# Output_Register.net
KiCad netlist of a schematic drawn in EasyEDA Pro
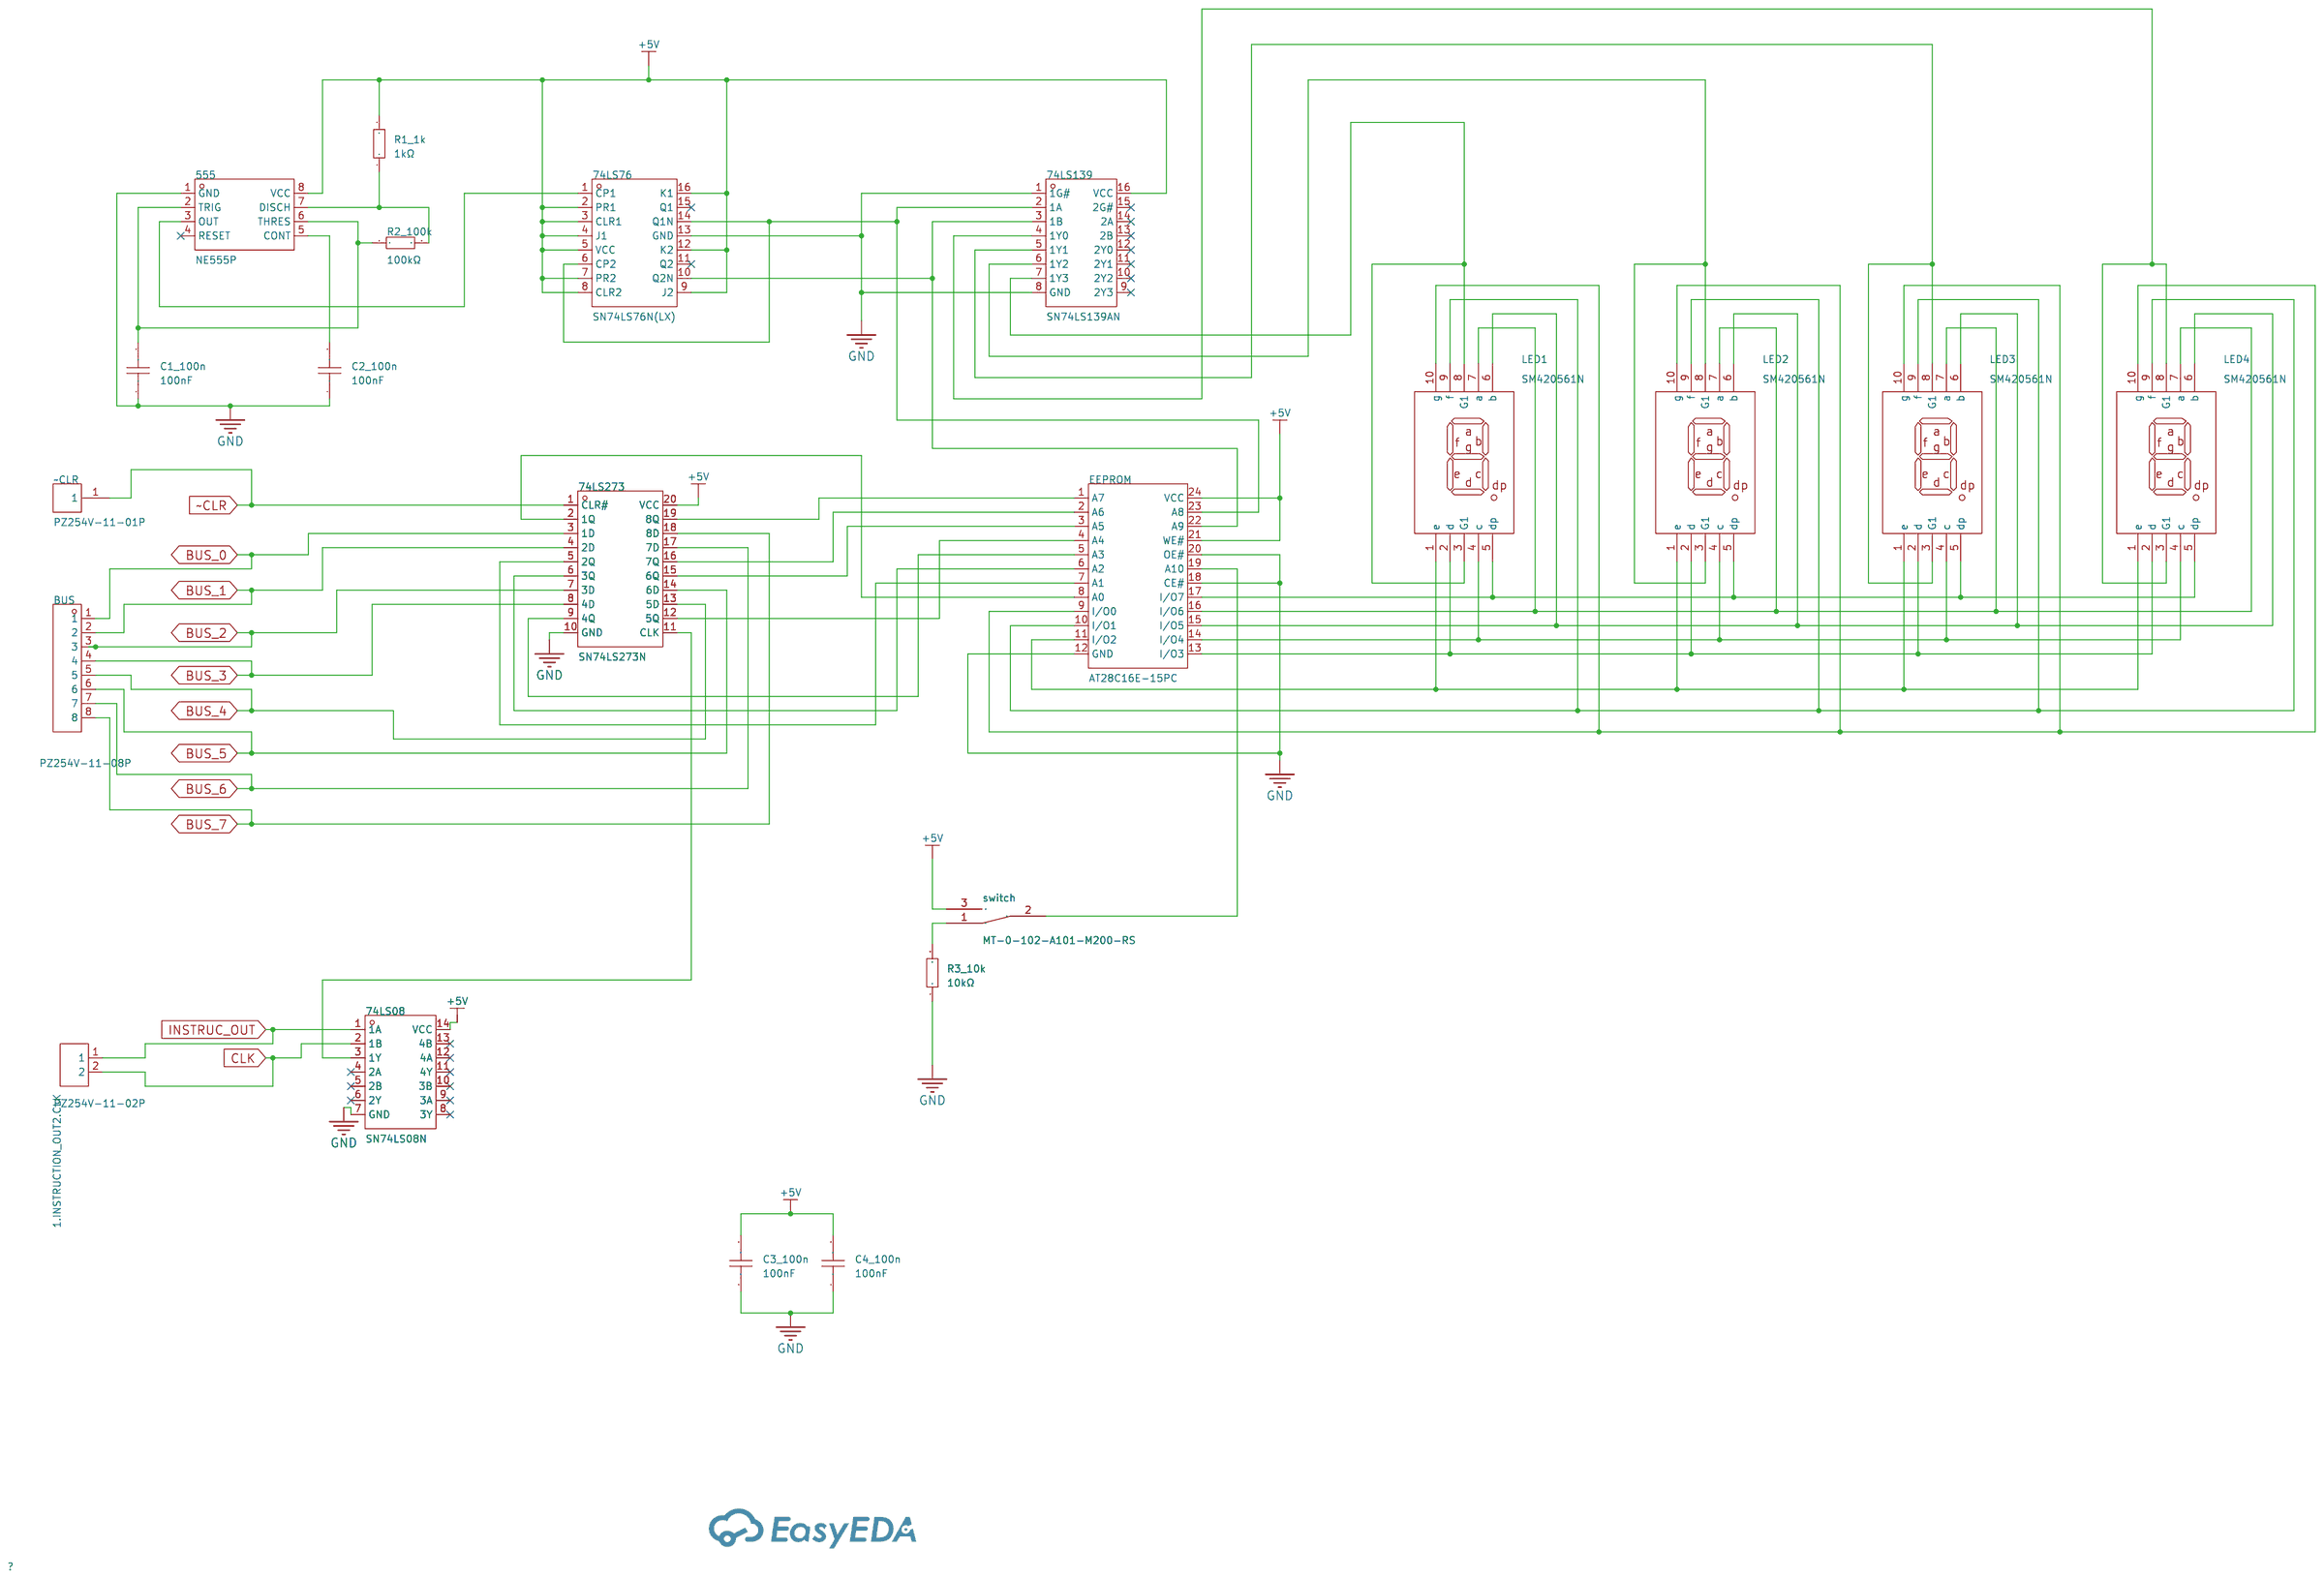
[diagram p0: schematic sheet]

(export (version "E")
  (design (tool "Eeschema 10.0.6"))
  (components
    (comp (ref "1.INSTRUCTION_OUT2.CLK")
      (value "PZ254V-11-02P")
      (footprint "easyedapro:HDR-TH_2P-P2.54-V-M")
      (fields (field (name "Manufacturer") "XFCN(兴飞)"))
      (libsource (lib "easyedapro") (part "PZ254V-11-02P"))
    )
    (comp (ref "74LS08")
      (value "SN74LS08N")
      (footprint "easyedapro:PDIP-14_L19.3-W6.4-P2.54-LS7.9-BL-1")
      (fields (field (name "Manufacturer") "TI(德州仪器)"))
      (libsource (lib "easyedapro") (part "SN74LS08N"))
    )
    (comp (ref "74LS76")
      (value "SN74LS76N(LX)")
      (footprint "easyedapro:PDIP-16_L19.3-W6.4-P2.54-LS7.94-BL")
      (fields (field (name "Manufacturer") "LX(灵星芯微)"))
      (libsource (lib "easyedapro") (part "SN74LS76N(LX)"))
    )
    (comp (ref "74LS139")
      (value "SN74LS139AN")
      (footprint "easyedapro:PDIP-16_L19.3-W6.4-P2.54-LS7.9-BL")
      (fields (field (name "Manufacturer") "TI(德州仪器)"))
      (libsource (lib "easyedapro") (part "SN74LS139AN"))
    )
    (comp (ref "74LS273")
      (value "SN74LS273N")
      (footprint "easyedapro:PDIP-20_L25.4-W6.4-P2.54-LS7.6-BL")
      (fields (field (name "Manufacturer") "TI(德州仪器)"))
      (libsource (lib "easyedapro") (part "SN74LS273N"))
    )
    (comp (ref "555")
      (value "NE555P")
      (footprint "easyedapro:DIP-8_L9.8-W6.6-P2.54-LS7.6-BL")
      (fields (field (name "Manufacturer") "TI(德州仪器)"))
      (libsource (lib "easyedapro") (part "NE555P"))
    )
    (comp (ref "BUS")
      (value "PZ254V-11-08P")
      (footprint "easyedapro:HDR-TH_8P-P2.54-V-M")
      (fields (field (name "Manufacturer") "XFCN(兴飞)"))
      (libsource (lib "easyedapro") (part "PZ254V-11-08P"))
    )
    (comp (ref "C1_100n")
      (value "100nF")
      (footprint "easyedapro:CAP-TH_L8.5-W5.0-P5.00-D1.2")
      (fields (field (name "Manufacturer Part") "CT4-0805B104K500F3") (field (name "Manufacturer") "FH(风华)"))
      (libsource (lib "easyedapro") (part "CT4-0805B104K500F3"))
    )
    (comp (ref "C2_100n")
      (value "100nF")
      (footprint "easyedapro:CAP-TH_L8.5-W5.0-P5.00-D1.2")
      (fields (field (name "Manufacturer Part") "CT4-0805B104K500F3") (field (name "Manufacturer") "FH(风华)"))
      (libsource (lib "easyedapro") (part "CT4-0805B104K500F3"))
    )
    (comp (ref "C3_100n")
      (value "100nF")
      (footprint "easyedapro:CAP-TH_L8.5-W5.0-P5.00-D1.2")
      (fields (field (name "Manufacturer Part") "CT4-0805B104K500F3") (field (name "Manufacturer") "FH(风华)"))
      (libsource (lib "easyedapro") (part "CT4-0805B104K500F3"))
    )
    (comp (ref "C4_100n")
      (value "100nF")
      (footprint "easyedapro:CAP-TH_L8.5-W5.0-P5.00-D1.2")
      (fields (field (name "Manufacturer Part") "CT4-0805B104K500F3") (field (name "Manufacturer") "FH(风华)"))
      (libsource (lib "easyedapro") (part "CT4-0805B104K500F3"))
    )
    (comp (ref "EEPROM")
      (value "AT28C16E-15PC")
      (footprint "easyedapro:PDIP-24_L31.0-W13.5-P2.54-LS15.2-BL")
      (fields (field (name "Manufacturer") "MICROCHIP(美国微芯)"))
      (libsource (lib "easyedapro") (part "AT28C16E-15PC"))
    )
    (comp (ref "LED1")
      (value "SM420561N")
      (footprint "easyedapro:LED-SEG-TH_10P-L12.7-W19.0-P2.54-S15.24-BL")
      (fields (field (name "Manufacturer") "ARKLED(方舟)"))
      (libsource (lib "easyedapro") (part "SM420561N"))
    )
    (comp (ref "LED2")
      (value "SM420561N")
      (footprint "easyedapro:LED-SEG-TH_10P-L12.7-W19.0-P2.54-S15.24-BL")
      (fields (field (name "Manufacturer") "ARKLED(方舟)"))
      (libsource (lib "easyedapro") (part "SM420561N"))
    )
    (comp (ref "LED3")
      (value "SM420561N")
      (footprint "easyedapro:LED-SEG-TH_10P-L12.7-W19.0-P2.54-S15.24-BL")
      (fields (field (name "Manufacturer") "ARKLED(方舟)"))
      (libsource (lib "easyedapro") (part "SM420561N"))
    )
    (comp (ref "LED4")
      (value "SM420561N")
      (footprint "easyedapro:LED-SEG-TH_10P-L12.7-W19.0-P2.54-S15.24-BL")
      (fields (field (name "Manufacturer") "ARKLED(方舟)"))
      (libsource (lib "easyedapro") (part "SM420561N"))
    )
    (comp (ref "R1_1k")
      (value "1kΩ")
      (footprint "easyedapro:R_AXIAL-0.4")
      (libsource (lib "easyedapro") (part "Res"))
    )
    (comp (ref "R2_100k")
      (value "100kΩ")
      (footprint "easyedapro:R_AXIAL-0.4")
      (libsource (lib "easyedapro") (part "Res"))
    )
    (comp (ref "R3_10k")
      (value "10kΩ")
      (footprint "easyedapro:R_AXIAL-0.4")
      (libsource (lib "easyedapro") (part "Res"))
    )
    (comp (ref "switch")
      (value "MT-0-102-A101-M200-RS")
      (footprint "easyedapro:SW-TH_MT-0-103-A101-M200-RS")
      (fields (field (name "Manufacturer") "YUEN FUNG(源丰)"))
      (libsource (lib "easyedapro") (part "MT-0-102-A101-M200-RS+PJ"))
    )
    (comp (ref "~CLR")
      (value "PZ254V-11-01P")
      (footprint "easyedapro:HDR-TH_1P-P2.54-V-M")
      (fields (field (name "Manufacturer") "XFCN(兴飞)"))
      (libsource (lib "easyedapro") (part "PZ254V-11-01P"))
    )
  )
  (nets
    (net (code "1") (name "+5V") (class "Default")
      (node (ref "555") (pin "8") (pinfunction "VCC_8") (pintype "input"))
      (node (ref "74LS08") (pin "14") (pinfunction "VCC_14") (pintype "unspecified"))
      (node (ref "74LS139") (pin "16") (pinfunction "VCC_16") (pintype "input"))
      (node (ref "74LS273") (pin "20") (pinfunction "VCC_20") (pintype "unspecified"))
      (node (ref "74LS76") (pin "12") (pinfunction "K2_12") (pintype "unspecified"))
      (node (ref "74LS76") (pin "16") (pinfunction "K1_16") (pintype "unspecified"))
      (node (ref "74LS76") (pin "2") (pinfunction "PR1_2") (pintype "unspecified"))
      (node (ref "74LS76") (pin "3") (pinfunction "CLR1_3") (pintype "unspecified"))
      (node (ref "74LS76") (pin "4") (pinfunction "J1_4") (pintype "unspecified"))
      (node (ref "74LS76") (pin "5") (pinfunction "VCC_5") (pintype "unspecified"))
      (node (ref "74LS76") (pin "7") (pinfunction "PR2_7") (pintype "unspecified"))
      (node (ref "74LS76") (pin "8") (pinfunction "CLR2_8") (pintype "unspecified"))
      (node (ref "74LS76") (pin "9") (pinfunction "J2_9") (pintype "unspecified"))
      (node (ref "C3_100n") (pin "2") (pinfunction "2_2") (pintype "unspecified"))
      (node (ref "C4_100n") (pin "2") (pinfunction "2_2") (pintype "unspecified"))
      (node (ref "EEPROM") (pin "21") (pinfunction "WE#_21") (pintype "unspecified"))
      (node (ref "EEPROM") (pin "24") (pinfunction "VCC_24") (pintype "unspecified"))
      (node (ref "R1_1k") (pin "2") (pinfunction "2_2") (pintype "input"))
      (node (ref "switch") (pin "3") (pinfunction "3_3") (pintype "unspecified"))
    )
    (net (code "2") (name "BUS_0") (class "Default")
      (node (ref "74LS273") (pin "3") (pinfunction "1D_3") (pintype "unspecified"))
      (node (ref "BUS") (pin "1") (pinfunction "1_1") (pintype "unspecified"))
    )
    (net (code "3") (name "BUS_1") (class "Default")
      (node (ref "74LS273") (pin "4") (pinfunction "2D_4") (pintype "unspecified"))
      (node (ref "BUS") (pin "2") (pinfunction "2_2") (pintype "unspecified"))
    )
    (net (code "4") (name "BUS_2") (class "Default")
      (node (ref "74LS273") (pin "7") (pinfunction "3D_7") (pintype "unspecified"))
      (node (ref "BUS") (pin "3") (pinfunction "3_3") (pintype "unspecified"))
    )
    (net (code "5") (name "BUS_3") (class "Default")
      (node (ref "74LS273") (pin "8") (pinfunction "4D_8") (pintype "unspecified"))
      (node (ref "BUS") (pin "4") (pinfunction "4_4") (pintype "unspecified"))
    )
    (net (code "6") (name "BUS_4") (class "Default")
      (node (ref "74LS273") (pin "13") (pinfunction "5D_13") (pintype "unspecified"))
      (node (ref "BUS") (pin "5") (pinfunction "5_5") (pintype "unspecified"))
    )
    (net (code "7") (name "BUS_5") (class "Default")
      (node (ref "74LS273") (pin "14") (pinfunction "6D_14") (pintype "unspecified"))
      (node (ref "BUS") (pin "6") (pinfunction "6_6") (pintype "unspecified"))
    )
    (net (code "8") (name "BUS_6") (class "Default")
      (node (ref "74LS273") (pin "17") (pinfunction "7D_17") (pintype "unspecified"))
      (node (ref "BUS") (pin "7") (pinfunction "7_7") (pintype "unspecified"))
    )
    (net (code "9") (name "BUS_7") (class "Default")
      (node (ref "74LS273") (pin "18") (pinfunction "8D_18") (pintype "unspecified"))
      (node (ref "BUS") (pin "8") (pinfunction "8_8") (pintype "unspecified"))
    )
    (net (code "10") (name "CLK") (class "Default")
      (node (ref "1.INSTRUCTION_OUT2.CLK") (pin "2") (pinfunction "2_2") (pintype "unspecified"))
      (node (ref "74LS08") (pin "2") (pinfunction "1B_2") (pintype "unspecified"))
    )
    (net (code "11") (name "GND") (class "Default")
      (node (ref "555") (pin "1") (pinfunction "GND_1") (pintype "input"))
      (node (ref "74LS08") (pin "7") (pinfunction "GND_7") (pintype "unspecified"))
      (node (ref "74LS139") (pin "1") (pinfunction "1G#_1") (pintype "input"))
      (node (ref "74LS139") (pin "8") (pinfunction "GND_8") (pintype "input"))
      (node (ref "74LS273") (pin "10") (pinfunction "GND_10") (pintype "unspecified"))
      (node (ref "74LS76") (pin "13") (pinfunction "GND_13") (pintype "unspecified"))
      (node (ref "C1_100n") (pin "1") (pinfunction "1_1") (pintype "unspecified"))
      (node (ref "C2_100n") (pin "1") (pinfunction "1_1") (pintype "unspecified"))
      (node (ref "C3_100n") (pin "1") (pinfunction "1_1") (pintype "unspecified"))
      (node (ref "C4_100n") (pin "1") (pinfunction "1_1") (pintype "unspecified"))
      (node (ref "EEPROM") (pin "12") (pinfunction "GND_12") (pintype "unspecified"))
      (node (ref "EEPROM") (pin "18") (pinfunction "CE#_18") (pintype "unspecified"))
      (node (ref "EEPROM") (pin "20") (pinfunction "OE#_20") (pintype "unspecified"))
      (node (ref "R3_10k") (pin "1") (pinfunction "1_1") (pintype "input"))
    )
    (net (code "12") (name "INSTRUC_OUT") (class "Default")
      (node (ref "1.INSTRUCTION_OUT2.CLK") (pin "1") (pinfunction "1_1") (pintype "unspecified"))
      (node (ref "74LS08") (pin "1") (pinfunction "1A_1") (pintype "unspecified"))
    )
    (net (code "13") (name "Net-(74LS08-1Y)") (class "Default")
      (node (ref "74LS08") (pin "3") (pinfunction "1Y_3") (pintype "unspecified"))
      (node (ref "74LS273") (pin "11") (pinfunction "CLK_11") (pintype "unspecified"))
    )
    (net (code "14") (name "Net-(74LS139-1A)") (class "Default")
      (node (ref "74LS139") (pin "2") (pinfunction "1A_2") (pintype "input"))
      (node (ref "74LS76") (pin "14") (pinfunction "Q1N_14") (pintype "unspecified"))
      (node (ref "74LS76") (pin "6") (pinfunction "CP2_6") (pintype "unspecified"))
      (node (ref "EEPROM") (pin "23") (pinfunction "A8_23") (pintype "unspecified"))
    )
    (net (code "15") (name "Net-(74LS139-1B)") (class "Default")
      (node (ref "74LS139") (pin "3") (pinfunction "1B_3") (pintype "input"))
      (node (ref "74LS76") (pin "10") (pinfunction "Q2N_10") (pintype "unspecified"))
      (node (ref "EEPROM") (pin "22") (pinfunction "A9_22") (pintype "unspecified"))
    )
    (net (code "16") (name "Net-(74LS139-1Y0)") (class "Default")
      (node (ref "74LS139") (pin "4") (pinfunction "1Y0_4") (pintype "input"))
      (node (ref "LED4") (pin "3") (pinfunction "G1_3") (pintype "input"))
      (node (ref "LED4") (pin "8") (pinfunction "G1_8") (pintype "input"))
    )
    (net (code "17") (name "Net-(74LS139-1Y1)") (class "Default")
      (node (ref "74LS139") (pin "5") (pinfunction "1Y1_5") (pintype "input"))
      (node (ref "LED3") (pin "3") (pinfunction "G1_3") (pintype "input"))
      (node (ref "LED3") (pin "8") (pinfunction "G1_8") (pintype "input"))
    )
    (net (code "18") (name "Net-(74LS139-1Y2)") (class "Default")
      (node (ref "74LS139") (pin "6") (pinfunction "1Y2_6") (pintype "input"))
      (node (ref "LED2") (pin "3") (pinfunction "G1_3") (pintype "input"))
      (node (ref "LED2") (pin "8") (pinfunction "G1_8") (pintype "input"))
    )
    (net (code "19") (name "Net-(74LS139-1Y3)") (class "Default")
      (node (ref "74LS139") (pin "7") (pinfunction "1Y3_7") (pintype "input"))
      (node (ref "LED1") (pin "3") (pinfunction "G1_3") (pintype "input"))
      (node (ref "LED1") (pin "8") (pinfunction "G1_8") (pintype "input"))
    )
    (net (code "20") (name "Net-(74LS273-1Q)") (class "Default")
      (node (ref "74LS273") (pin "2") (pinfunction "1Q_2") (pintype "unspecified"))
      (node (ref "EEPROM") (pin "8") (pinfunction "A0_8") (pintype "unspecified"))
    )
    (net (code "21") (name "Net-(74LS273-2Q)") (class "Default")
      (node (ref "74LS273") (pin "5") (pinfunction "2Q_5") (pintype "unspecified"))
      (node (ref "EEPROM") (pin "7") (pinfunction "A1_7") (pintype "unspecified"))
    )
    (net (code "22") (name "Net-(74LS273-3Q)") (class "Default")
      (node (ref "74LS273") (pin "6") (pinfunction "3Q_6") (pintype "unspecified"))
      (node (ref "EEPROM") (pin "6") (pinfunction "A2_6") (pintype "unspecified"))
    )
    (net (code "23") (name "Net-(74LS273-4Q)") (class "Default")
      (node (ref "74LS273") (pin "9") (pinfunction "4Q_9") (pintype "unspecified"))
      (node (ref "EEPROM") (pin "5") (pinfunction "A3_5") (pintype "unspecified"))
    )
    (net (code "24") (name "Net-(74LS273-5Q)") (class "Default")
      (node (ref "74LS273") (pin "12") (pinfunction "5Q_12") (pintype "unspecified"))
      (node (ref "EEPROM") (pin "4") (pinfunction "A4_4") (pintype "unspecified"))
    )
    (net (code "25") (name "Net-(74LS273-6Q)") (class "Default")
      (node (ref "74LS273") (pin "15") (pinfunction "6Q_15") (pintype "unspecified"))
      (node (ref "EEPROM") (pin "3") (pinfunction "A5_3") (pintype "unspecified"))
    )
    (net (code "26") (name "Net-(74LS273-7Q)") (class "Default")
      (node (ref "74LS273") (pin "16") (pinfunction "7Q_16") (pintype "unspecified"))
      (node (ref "EEPROM") (pin "2") (pinfunction "A6_2") (pintype "unspecified"))
    )
    (net (code "27") (name "Net-(74LS273-8Q)") (class "Default")
      (node (ref "74LS273") (pin "19") (pinfunction "8Q_19") (pintype "unspecified"))
      (node (ref "EEPROM") (pin "1") (pinfunction "A7_1") (pintype "unspecified"))
    )
    (net (code "28") (name "Net-(555-CONT)") (class "Default")
      (node (ref "555") (pin "5") (pinfunction "CONT_5") (pintype "input"))
      (node (ref "C2_100n") (pin "2") (pinfunction "2_2") (pintype "unspecified"))
    )
    (net (code "29") (name "Net-(555-DISCH)") (class "Default")
      (node (ref "555") (pin "7") (pinfunction "DISCH_7") (pintype "input"))
      (node (ref "R1_1k") (pin "1") (pinfunction "1_1") (pintype "input"))
      (node (ref "R2_100k") (pin "2") (pinfunction "2_2") (pintype "input"))
    )
    (net (code "30") (name "Net-(555-OUT)") (class "Default")
      (node (ref "555") (pin "3") (pinfunction "OUT_3") (pintype "input"))
      (node (ref "74LS76") (pin "1") (pinfunction "CP1_1") (pintype "unspecified"))
    )
    (net (code "31") (name "Net-(555-THRES)") (class "Default")
      (node (ref "555") (pin "2") (pinfunction "TRIG_2") (pintype "input"))
      (node (ref "555") (pin "6") (pinfunction "THRES_6") (pintype "input"))
      (node (ref "C1_100n") (pin "2") (pinfunction "2_2") (pintype "unspecified"))
      (node (ref "R2_100k") (pin "1") (pinfunction "1_1") (pintype "input"))
    )
    (net (code "32") (name "Net-(EEPROM-A10)") (class "Default")
      (node (ref "EEPROM") (pin "19") (pinfunction "A10_19") (pintype "unspecified"))
      (node (ref "switch") (pin "2") (pinfunction "2_2") (pintype "unspecified"))
    )
    (net (code "33") (name "Net-(EEPROM-I{slash}O0)") (class "Default")
      (node (ref "EEPROM") (pin "9") (pinfunction "I/O0_9") (pintype "unspecified"))
      (node (ref "LED1") (pin "10") (pinfunction "g_10") (pintype "input"))
      (node (ref "LED2") (pin "10") (pinfunction "g_10") (pintype "input"))
      (node (ref "LED3") (pin "10") (pinfunction "g_10") (pintype "input"))
      (node (ref "LED4") (pin "10") (pinfunction "g_10") (pintype "input"))
    )
    (net (code "34") (name "Net-(EEPROM-I{slash}O1)") (class "Default")
      (node (ref "EEPROM") (pin "10") (pinfunction "I/O1_10") (pintype "unspecified"))
      (node (ref "LED1") (pin "9") (pinfunction "f_9") (pintype "input"))
      (node (ref "LED2") (pin "9") (pinfunction "f_9") (pintype "input"))
      (node (ref "LED3") (pin "9") (pinfunction "f_9") (pintype "input"))
      (node (ref "LED4") (pin "9") (pinfunction "f_9") (pintype "input"))
    )
    (net (code "35") (name "Net-(EEPROM-I{slash}O2)") (class "Default")
      (node (ref "EEPROM") (pin "11") (pinfunction "I/O2_11") (pintype "unspecified"))
      (node (ref "LED1") (pin "1") (pinfunction "e_1") (pintype "input"))
      (node (ref "LED2") (pin "1") (pinfunction "e_1") (pintype "input"))
      (node (ref "LED3") (pin "1") (pinfunction "e_1") (pintype "input"))
      (node (ref "LED4") (pin "1") (pinfunction "e_1") (pintype "input"))
    )
    (net (code "36") (name "Net-(EEPROM-I{slash}O3)") (class "Default")
      (node (ref "EEPROM") (pin "13") (pinfunction "I/O3_13") (pintype "unspecified"))
      (node (ref "LED1") (pin "2") (pinfunction "d_2") (pintype "input"))
      (node (ref "LED2") (pin "2") (pinfunction "d_2") (pintype "input"))
      (node (ref "LED3") (pin "2") (pinfunction "d_2") (pintype "input"))
      (node (ref "LED4") (pin "2") (pinfunction "d_2") (pintype "input"))
    )
    (net (code "37") (name "Net-(EEPROM-I{slash}O4)") (class "Default")
      (node (ref "EEPROM") (pin "14") (pinfunction "I/O4_14") (pintype "unspecified"))
      (node (ref "LED1") (pin "4") (pinfunction "c_4") (pintype "input"))
      (node (ref "LED2") (pin "4") (pinfunction "c_4") (pintype "input"))
      (node (ref "LED3") (pin "4") (pinfunction "c_4") (pintype "input"))
      (node (ref "LED4") (pin "4") (pinfunction "c_4") (pintype "input"))
    )
    (net (code "38") (name "Net-(EEPROM-I{slash}O5)") (class "Default")
      (node (ref "EEPROM") (pin "15") (pinfunction "I/O5_15") (pintype "unspecified"))
      (node (ref "LED1") (pin "6") (pinfunction "b_6") (pintype "input"))
      (node (ref "LED2") (pin "6") (pinfunction "b_6") (pintype "input"))
      (node (ref "LED3") (pin "6") (pinfunction "b_6") (pintype "input"))
      (node (ref "LED4") (pin "6") (pinfunction "b_6") (pintype "input"))
    )
    (net (code "39") (name "Net-(EEPROM-I{slash}O6)") (class "Default")
      (node (ref "EEPROM") (pin "16") (pinfunction "I/O6_16") (pintype "unspecified"))
      (node (ref "LED1") (pin "7") (pinfunction "a_7") (pintype "input"))
      (node (ref "LED2") (pin "7") (pinfunction "a_7") (pintype "input"))
      (node (ref "LED3") (pin "7") (pinfunction "a_7") (pintype "input"))
      (node (ref "LED4") (pin "7") (pinfunction "a_7") (pintype "input"))
    )
    (net (code "40") (name "Net-(EEPROM-I{slash}O7)") (class "Default")
      (node (ref "EEPROM") (pin "17") (pinfunction "I/O7_17") (pintype "unspecified"))
      (node (ref "LED1") (pin "5") (pinfunction "dp_5") (pintype "input"))
      (node (ref "LED2") (pin "5") (pinfunction "dp_5") (pintype "input"))
      (node (ref "LED3") (pin "5") (pinfunction "dp_5") (pintype "input"))
      (node (ref "LED4") (pin "5") (pinfunction "dp_5") (pintype "input"))
    )
    (net (code "41") (name "Net-(R3_10k-Pad2)") (class "Default")
      (node (ref "R3_10k") (pin "2") (pinfunction "2_2") (pintype "input"))
      (node (ref "switch") (pin "1") (pinfunction "1_1") (pintype "unspecified"))
    )
    (net (code "42") (name "unconnected-(74LS08-2A-Pad4)") (class "Default")
      (node (ref "74LS08") (pin "4") (pinfunction "2A_4") (pintype "unspecified+no_connect"))
    )
    (net (code "43") (name "unconnected-(74LS08-2B-Pad5)") (class "Default")
      (node (ref "74LS08") (pin "5") (pinfunction "2B_5") (pintype "unspecified+no_connect"))
    )
    (net (code "44") (name "unconnected-(74LS08-2Y-Pad6)") (class "Default")
      (node (ref "74LS08") (pin "6") (pinfunction "2Y_6") (pintype "unspecified+no_connect"))
    )
    (net (code "45") (name "unconnected-(74LS08-3A-Pad9)") (class "Default")
      (node (ref "74LS08") (pin "9") (pinfunction "3A_9") (pintype "unspecified+no_connect"))
    )
    (net (code "46") (name "unconnected-(74LS08-3B-Pad10)") (class "Default")
      (node (ref "74LS08") (pin "10") (pinfunction "3B_10") (pintype "unspecified+no_connect"))
    )
    (net (code "47") (name "unconnected-(74LS08-3Y-Pad8)") (class "Default")
      (node (ref "74LS08") (pin "8") (pinfunction "3Y_8") (pintype "unspecified+no_connect"))
    )
    (net (code "48") (name "unconnected-(74LS08-4A-Pad12)") (class "Default")
      (node (ref "74LS08") (pin "12") (pinfunction "4A_12") (pintype "unspecified+no_connect"))
    )
    (net (code "49") (name "unconnected-(74LS08-4B-Pad13)") (class "Default")
      (node (ref "74LS08") (pin "13") (pinfunction "4B_13") (pintype "unspecified+no_connect"))
    )
    (net (code "50") (name "unconnected-(74LS08-4Y-Pad11)") (class "Default")
      (node (ref "74LS08") (pin "11") (pinfunction "4Y_11") (pintype "unspecified+no_connect"))
    )
    (net (code "51") (name "unconnected-(74LS76-Q1-Pad15)") (class "Default")
      (node (ref "74LS76") (pin "15") (pinfunction "Q1_15") (pintype "unspecified+no_connect"))
    )
    (net (code "52") (name "unconnected-(74LS76-Q2-Pad11)") (class "Default")
      (node (ref "74LS76") (pin "11") (pinfunction "Q2_11") (pintype "unspecified+no_connect"))
    )
    (net (code "53") (name "unconnected-(74LS139-2A-Pad14)") (class "Default")
      (node (ref "74LS139") (pin "14") (pinfunction "2A_14") (pintype "input+no_connect"))
    )
    (net (code "54") (name "unconnected-(74LS139-2B-Pad13)") (class "Default")
      (node (ref "74LS139") (pin "13") (pinfunction "2B_13") (pintype "input+no_connect"))
    )
    (net (code "55") (name "unconnected-(74LS139-2G#-Pad15)") (class "Default")
      (node (ref "74LS139") (pin "15") (pinfunction "2G#_15") (pintype "input+no_connect"))
    )
    (net (code "56") (name "unconnected-(74LS139-2Y0-Pad12)") (class "Default")
      (node (ref "74LS139") (pin "12") (pinfunction "2Y0_12") (pintype "input+no_connect"))
    )
    (net (code "57") (name "unconnected-(74LS139-2Y1-Pad11)") (class "Default")
      (node (ref "74LS139") (pin "11") (pinfunction "2Y1_11") (pintype "input+no_connect"))
    )
    (net (code "58") (name "unconnected-(74LS139-2Y2-Pad10)") (class "Default")
      (node (ref "74LS139") (pin "10") (pinfunction "2Y2_10") (pintype "input+no_connect"))
    )
    (net (code "59") (name "unconnected-(74LS139-2Y3-Pad9)") (class "Default")
      (node (ref "74LS139") (pin "9") (pinfunction "2Y3_9") (pintype "input+no_connect"))
    )
    (net (code "60") (name "unconnected-(555-RESET-Pad4)") (class "Default")
      (node (ref "555") (pin "4") (pinfunction "RESET_4") (pintype "input+no_connect"))
    )
    (net (code "61") (name "~CLR") (class "Default")
      (node (ref "74LS273") (pin "1") (pinfunction "CLR#_1") (pintype "unspecified"))
      (node (ref "~CLR") (pin "1") (pinfunction "1_1") (pintype "unspecified"))
    )
  )
)
